# YakupTrkn2.net
KiCad netlist of a schematic drawn in Altium Designer
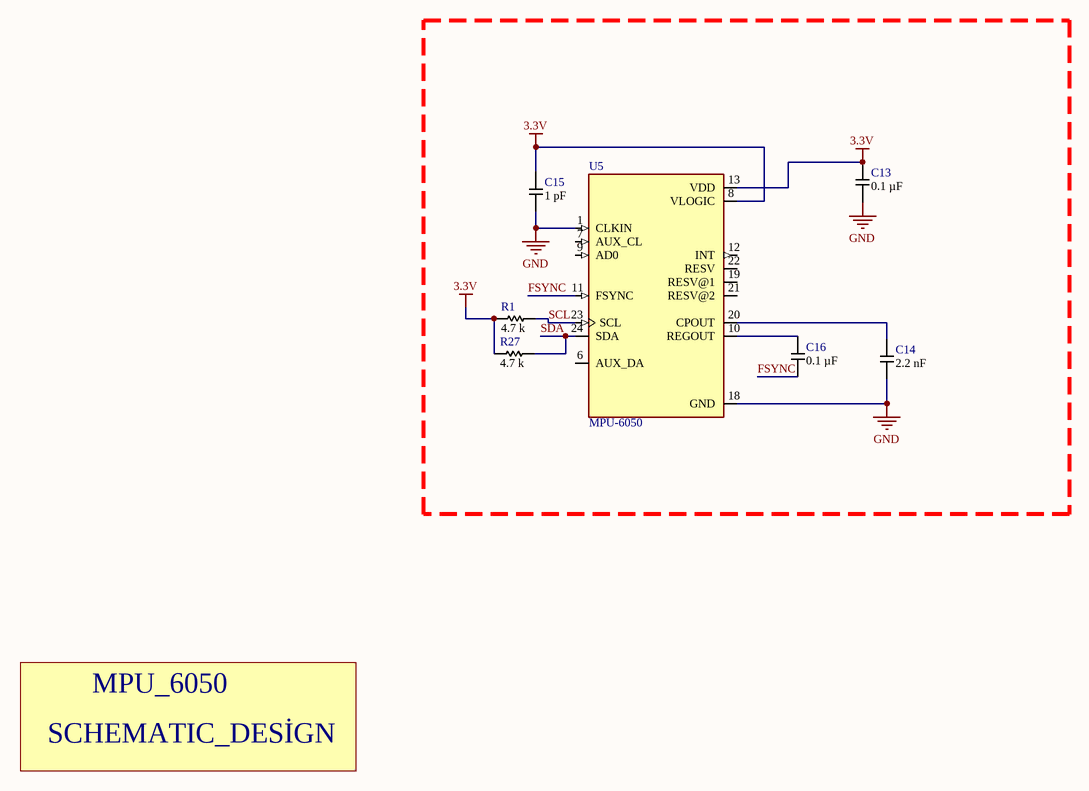
[diagram p0: YakupTrkn2.SchDoc]

(export (version "E")
  (design (tool "Eeschema 10.0.6"))
  (components
    (comp (ref "C13")
      (value "CL21B104MACNNNC")
      (footprint "SAMSUNG_CAP_0805_095")
      (description "CAP CER 0.1UF 25V X7R 0805")
      (fields (field (name "CAPACITANCE") "0.1 µF"))
      (libsource (lib "YakupTrkn") (part "CL21B104MACNNNC"))
    )
    (comp (ref "C14")
      (value "CL21B222KBANNNC_1")
      (footprint "SAMSUNG_CAP_0805_075")
      (description "CAP CER 2200PF 50V X7R 0805")
      (fields (field (name "CAPACITANCE") "2.2 nF"))
      (libsource (lib "YakupTrkn") (part "CL21B222KBANNNC_1"))
    )
    (comp (ref "C15")
      (value "CL10C010BB8NNNC")
      (footprint "SAMSUNG_CAP_0603_090")
      (description "CAP CER 1PF 50V C0G/NP0 0603")
      (fields (field (name "CAPACITANCE") "1 pF"))
      (libsource (lib "YakupTrkn") (part "CL10C010BB8NNNC"))
    )
    (comp (ref "C16")
      (value "CL21B104MACNNNC")
      (footprint "SAMSUNG_CAP_0805_095")
      (description "CAP CER 0.1UF 25V X7R 0805")
      (fields (field (name "CAPACITANCE") "0.1 µF"))
      (libsource (lib "YakupTrkn") (part "CL21B104MACNNNC"))
    )
    (comp (ref "R1")
      (value "0603SAJ0472TDE")
      (footprint "ROYALOHM_RES_0603")
      (description "RES SMD 4.7K OHM 5% 1/10W 0603")
      (fields (field (name "RESISTANCE") "4.7 k"))
      (libsource (lib "YakupTrkn") (part "0603SAJ0472TDE"))
    )
    (comp (ref "R27")
      (value "0603SAJ0472TDE")
      (footprint "ROYALOHM_RES_0603")
      (description "RES SMD 4.7K OHM 5% 1/10W 0603")
      (fields (field (name "RESISTANCE") "4.7 k"))
      (libsource (lib "YakupTrkn") (part "0603SAJ0472TDE"))
    )
    (comp (ref "U5")
      (value "MPU-6050")
      (footprint "MPU-6050:QFN50P400X400X95-24N")
      (description "MPU-6050 Six-Axis (Gyro + Accelerometer) MEMS MotionTrackingâ„¢ Devices")
      (fields (field (name "MF") "{'manufacturer': u'TDK InvenSense'}"))
      (libsource (lib "YakupTrkn") (part "MPU-6050"))
    )
  )
  (nets
    (net (code "1") (name "/FSYNC") (class "Default")
      (node (ref "C16") (pin "1") (pinfunction "1_1") (pintype "passive"))
      (node (ref "U5") (pin "11") (pinfunction "FSYNC_11") (pintype "input"))
    )
    (net (code "2") (name "/SCL") (class "Default")
      (node (ref "R1") (pin "2") (pinfunction "2_2") (pintype "passive"))
      (node (ref "U5") (pin "23") (pinfunction "SCL_23") (pintype "input"))
    )
    (net (code "3") (name "/SDA") (class "Default")
      (node (ref "R27") (pin "1") (pinfunction "1_1") (pintype "passive"))
      (node (ref "U5") (pin "24") (pinfunction "SDA_24") (pintype "bidirectional"))
    )
    (net (code "4") (name "3.3V") (class "Default")
      (node (ref "C13") (pin "2") (pinfunction "2_2") (pintype "passive"))
      (node (ref "C15") (pin "2") (pinfunction "2_2") (pintype "passive"))
      (node (ref "R1") (pin "1") (pinfunction "1_1") (pintype "passive"))
      (node (ref "R27") (pin "2") (pinfunction "2_2") (pintype "passive"))
      (node (ref "U5") (pin "13") (pinfunction "VDD_13") (pintype "power_in"))
      (node (ref "U5") (pin "8") (pinfunction "VLOGIC_8") (pintype "power_in"))
    )
    (net (code "5") (name "GND") (class "Default")
      (node (ref "C13") (pin "1") (pinfunction "1_1") (pintype "passive"))
      (node (ref "C14") (pin "1") (pinfunction "1_1") (pintype "passive"))
      (node (ref "C15") (pin "1") (pinfunction "1_1") (pintype "passive"))
      (node (ref "U5") (pin "1") (pinfunction "CLKIN_1") (pintype "input"))
      (node (ref "U5") (pin "18") (pinfunction "GND_18") (pintype "power_in"))
    )
    (net (code "6") (name "Net-(U5-CPOUT)") (class "Default")
      (node (ref "C14") (pin "2") (pinfunction "2_2") (pintype "passive"))
      (node (ref "U5") (pin "20") (pinfunction "CPOUT_20") (pintype "passive"))
    )
    (net (code "7") (name "Net-(U5-REGOUT)") (class "Default")
      (node (ref "C16") (pin "2") (pinfunction "2_2") (pintype "passive"))
      (node (ref "U5") (pin "10") (pinfunction "REGOUT_10") (pintype "passive"))
    )
    (net (code "8") (name "unconnected-(U5-AD0-Pad9)") (class "Default")
      (node (ref "U5") (pin "9") (pinfunction "AD0_9") (pintype "input"))
    )
    (net (code "9") (name "unconnected-(U5-AUX_CL-Pad7)") (class "Default")
      (node (ref "U5") (pin "7") (pinfunction "AUX_CL_7") (pintype "input"))
    )
    (net (code "10") (name "unconnected-(U5-AUX_DA-Pad6)") (class "Default")
      (node (ref "U5") (pin "6") (pinfunction "AUX_DA_6") (pintype "bidirectional"))
    )
    (net (code "11") (name "unconnected-(U5-INT-Pad12)") (class "Default")
      (node (ref "U5") (pin "12") (pinfunction "INT_12") (pintype "output"))
    )
    (net (code "12") (name "unconnected-(U5-RESV-Pad22)") (class "Default")
      (node (ref "U5") (pin "22") (pinfunction "RESV_22") (pintype "passive"))
    )
    (net (code "13") (name "unconnected-(U5-RESV@1-Pad19)") (class "Default")
      (node (ref "U5") (pin "19") (pinfunction "RESV@1_19") (pintype "passive"))
    )
    (net (code "14") (name "unconnected-(U5-RESV@2-Pad21)") (class "Default")
      (node (ref "U5") (pin "21") (pinfunction "RESV@2_21") (pintype "passive"))
    )
  )
)
